# Adafruit_DC_Power_BFF.net
KiCad netlist of a schematic drawn in EAGLE
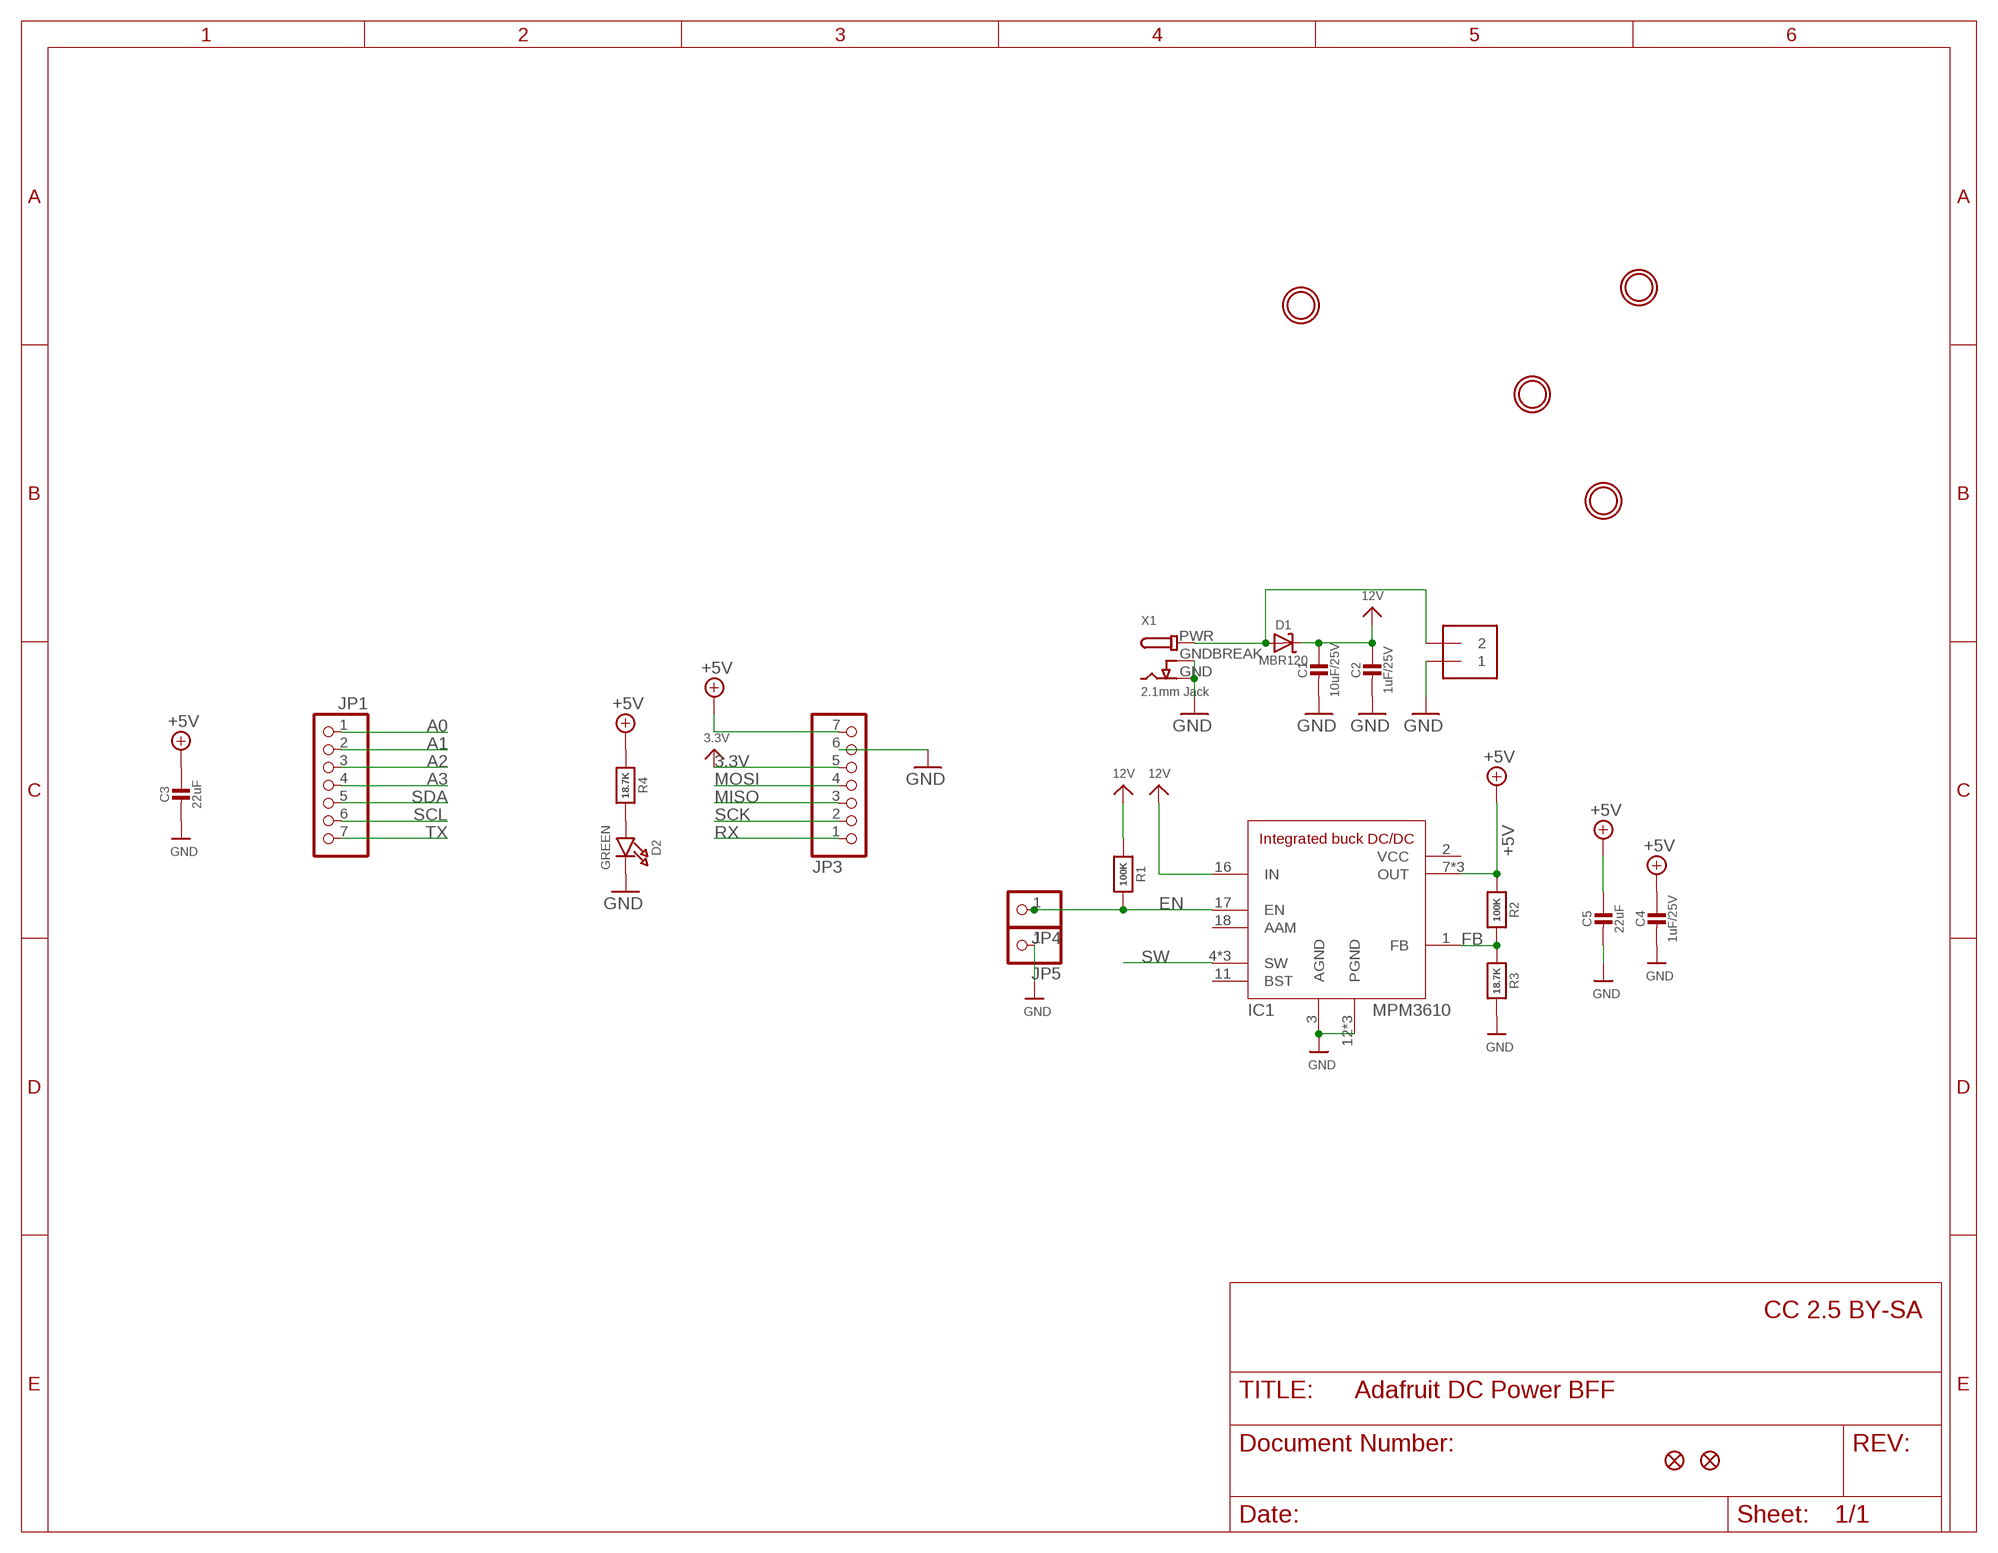
[diagram p0: schematic, sheet 1]

(export (version "E")
  (design (tool "Eeschema 10.0.6"))
  (components
    (comp (ref "C1")
      (value "10uF/25V")
      (footprint "eagle-import:0805-NO")
      (libsource (lib "eagle-import") (part "CAP_CERAMIC0805-NOOUTLINE"))
    )
    (comp (ref "C2")
      (value "1uF/25V")
      (footprint "eagle-import:0603-NO")
      (libsource (lib "eagle-import") (part "CAP_CERAMIC0603_NO"))
    )
    (comp (ref "C3")
      (value "22uF")
      (footprint "eagle-import:0805-NO")
      (libsource (lib "eagle-import") (part "CAP_CERAMIC0805-NOOUTLINE"))
    )
    (comp (ref "C4")
      (value "1uF/25V")
      (footprint "eagle-import:0603-NO")
      (libsource (lib "eagle-import") (part "CAP_CERAMIC0603_NO"))
    )
    (comp (ref "C5")
      (value "22uF")
      (footprint "eagle-import:0805-NO")
      (libsource (lib "eagle-import") (part "CAP_CERAMIC0805-NOOUTLINE"))
    )
    (comp (ref "D1")
      (value "MBR120")
      (footprint "eagle-import:SOD-123FL")
      (libsource (lib "eagle-import") (part "DIODE-SCHOTTKYSOD-123FL"))
    )
    (comp (ref "D2")
      (value "GREEN")
      (footprint "eagle-import:CHIPLED_0603_NOOUTLINE")
      (libsource (lib "eagle-import") (part "LED0603_NOOUTLINE"))
    )
    (comp (ref "IC1")
      (value "MPM3610")
      (footprint "eagle-import:MPM3610")
      (libsource (lib "eagle-import") (part "MPM3610"))
    )
    (comp (ref "J1")
      (value "1X2-3.5MM")
      (footprint "eagle-import:1X2-3.5MM")
      (libsource (lib "eagle-import") (part "1X2-3.5MM"))
    )
    (comp (ref "JP1")
      (value "HEADER-1X7THICKER")
      (footprint "eagle-import:1X07_ROUND_76")
      (libsource (lib "eagle-import") (part "HEADER-1X7THICKER"))
    )
    (comp (ref "JP3")
      (value "HEADER-1X7THICKER")
      (footprint "eagle-import:1X07_ROUND_76")
      (libsource (lib "eagle-import") (part "HEADER-1X7THICKER"))
    )
    (comp (ref "JP4")
      (value "HEADER-1X12MM")
      (footprint "eagle-import:1X01_2MM")
      (libsource (lib "eagle-import") (part "HEADER-1X12MM"))
    )
    (comp (ref "JP5")
      (value "HEADER-1X12MM")
      (footprint "eagle-import:1X01_2MM")
      (libsource (lib "eagle-import") (part "HEADER-1X12MM"))
    )
    (comp (ref "R1")
      (value "100K")
      (footprint "eagle-import:_0402NO")
      (libsource (lib "eagle-import") (part "RESISTOR_0402NO"))
    )
    (comp (ref "R2")
      (value "100K")
      (footprint "eagle-import:_0402NO")
      (libsource (lib "eagle-import") (part "RESISTOR_0402NO"))
    )
    (comp (ref "R3")
      (value "18.7K")
      (footprint "eagle-import:_0402NO")
      (libsource (lib "eagle-import") (part "RESISTOR_0402NO"))
    )
    (comp (ref "R4")
      (value "18.7K")
      (footprint "eagle-import:_0402NO")
      (libsource (lib "eagle-import") (part "RESISTOR_0402NO"))
    )
    (comp (ref "U$6")
      (value "FIDUCIAL_1MM")
      (footprint "eagle-import:FIDUCIAL_1MM")
      (libsource (lib "eagle-import") (part "FIDUCIAL_1MM"))
    )
    (comp (ref "U$8")
      (value "FIDUCIAL_1MM")
      (footprint "eagle-import:FIDUCIAL_1MM")
      (libsource (lib "eagle-import") (part "FIDUCIAL_1MM"))
    )
    (comp (ref "U$14")
      (value "MOUNTINGHOLE2.5")
      (footprint "eagle-import:MOUNTINGHOLE_2.5_PLATED")
      (libsource (lib "eagle-import") (part "MOUNTINGHOLE2.5"))
    )
    (comp (ref "U$15")
      (value "MOUNTINGHOLE2.5")
      (footprint "eagle-import:MOUNTINGHOLE_2.5_PLATED")
      (libsource (lib "eagle-import") (part "MOUNTINGHOLE2.5"))
    )
    (comp (ref "U$17")
      (value "MOUNTINGHOLE2.5")
      (footprint "eagle-import:MOUNTINGHOLE_2.5_PLATED")
      (libsource (lib "eagle-import") (part "MOUNTINGHOLE2.5"))
    )
    (comp (ref "U$18")
      (value "MOUNTINGHOLE2.5")
      (footprint "eagle-import:MOUNTINGHOLE_2.5_PLATED")
      (libsource (lib "eagle-import") (part "MOUNTINGHOLE2.5"))
    )
    (comp (ref "X1")
      (value "2.1mm Jack")
      (footprint "eagle-import:DCJACK_2MM_PTH")
      (libsource (lib "eagle-import") (part "DCBARRELPTH"))
    )
  )
  (nets
    (net (code "1") (name "+5V") (class "Default")
      (node (ref "C3") (pin "1") (pinfunction "1_1") (pintype "passive"))
      (node (ref "C4") (pin "1") (pinfunction "1_1") (pintype "passive"))
      (node (ref "C5") (pin "1") (pinfunction "1_1") (pintype "passive"))
      (node (ref "IC1") (pin "7") (pinfunction "OUT_7") (pintype "power_in"))
      (node (ref "IC1") (pin "8") (pinfunction "OUT_8") (pintype "power_in"))
      (node (ref "IC1") (pin "9") (pinfunction "OUT_9") (pintype "power_in"))
      (node (ref "JP3") (pin "7") (pinfunction "7_7") (pintype "passive"))
      (node (ref "R2") (pin "1") (pinfunction "1_1") (pintype "passive"))
      (node (ref "R4") (pin "1") (pinfunction "1_1") (pintype "passive"))
    )
    (net (code "2") (name "/A0") (class "Default")
      (node (ref "JP1") (pin "1") (pinfunction "1_1") (pintype "passive"))
    )
    (net (code "3") (name "/A1") (class "Default")
      (node (ref "JP1") (pin "2") (pinfunction "2_2") (pintype "passive"))
    )
    (net (code "4") (name "/A2") (class "Default")
      (node (ref "JP1") (pin "3") (pinfunction "3_3") (pintype "passive"))
    )
    (net (code "5") (name "/A3") (class "Default")
      (node (ref "JP1") (pin "4") (pinfunction "4_4") (pintype "passive"))
    )
    (net (code "6") (name "/EN") (class "Default")
      (node (ref "IC1") (pin "17") (pinfunction "EN_17") (pintype "input"))
      (node (ref "JP4") (pin "1") (pinfunction "1_1") (pintype "passive"))
      (node (ref "R1") (pin "2") (pinfunction "2_2") (pintype "passive"))
    )
    (net (code "7") (name "/FB") (class "Default")
      (node (ref "IC1") (pin "1") (pinfunction "FB_1") (pintype "input"))
      (node (ref "R2") (pin "2") (pinfunction "2_2") (pintype "passive"))
      (node (ref "R3") (pin "1") (pinfunction "1_1") (pintype "passive"))
    )
    (net (code "8") (name "/MISO") (class "Default")
      (node (ref "JP3") (pin "3") (pinfunction "3_3") (pintype "passive"))
    )
    (net (code "9") (name "/MOSI") (class "Default")
      (node (ref "JP3") (pin "4") (pinfunction "4_4") (pintype "passive"))
    )
    (net (code "10") (name "/RX") (class "Default")
      (node (ref "JP3") (pin "1") (pinfunction "1_1") (pintype "passive"))
    )
    (net (code "11") (name "/SCK") (class "Default")
      (node (ref "JP3") (pin "2") (pinfunction "2_2") (pintype "passive"))
    )
    (net (code "12") (name "/SCL") (class "Default")
      (node (ref "JP1") (pin "6") (pinfunction "6_6") (pintype "passive"))
    )
    (net (code "13") (name "/SDA") (class "Default")
      (node (ref "JP1") (pin "5") (pinfunction "5_5") (pintype "passive"))
    )
    (net (code "14") (name "/SW") (class "Default")
      (node (ref "IC1") (pin "4") (pinfunction "SW_4") (pintype "passive"))
      (node (ref "IC1") (pin "5") (pinfunction "SW_5") (pintype "passive"))
      (node (ref "IC1") (pin "6") (pinfunction "SW_6") (pintype "passive"))
    )
    (net (code "15") (name "/TX") (class "Default")
      (node (ref "JP1") (pin "7") (pinfunction "7_7") (pintype "passive"))
    )
    (net (code "16") (name "/VCC") (class "Default")
      (node (ref "IC1") (pin "2") (pinfunction "VCC_2") (pintype "power_in"))
    )
    (net (code "17") (name "3.3V") (class "Default")
      (node (ref "JP3") (pin "5") (pinfunction "5_5") (pintype "passive"))
    )
    (net (code "18") (name "12V") (class "Default")
      (node (ref "C1") (pin "1") (pinfunction "1_1") (pintype "passive"))
      (node (ref "C2") (pin "1") (pinfunction "1_1") (pintype "passive"))
      (node (ref "D1") (pin "C") (pinfunction "C_C") (pintype "passive"))
      (node (ref "IC1") (pin "16") (pinfunction "IN_16") (pintype "power_in"))
      (node (ref "R1") (pin "1") (pinfunction "1_1") (pintype "passive"))
    )
    (net (code "19") (name "GND") (class "Default")
      (node (ref "C1") (pin "2") (pinfunction "2_2") (pintype "passive"))
      (node (ref "C2") (pin "2") (pinfunction "2_2") (pintype "passive"))
      (node (ref "C3") (pin "2") (pinfunction "2_2") (pintype "passive"))
      (node (ref "C4") (pin "2") (pinfunction "2_2") (pintype "passive"))
      (node (ref "C5") (pin "2") (pinfunction "2_2") (pintype "passive"))
      (node (ref "D2") (pin "C") (pinfunction "C_C") (pintype "passive"))
      (node (ref "IC1") (pin "12") (pinfunction "PGND_12") (pintype "power_in"))
      (node (ref "IC1") (pin "13") (pinfunction "PGND_13") (pintype "power_in"))
      (node (ref "IC1") (pin "14") (pinfunction "PGND_14") (pintype "power_in"))
      (node (ref "IC1") (pin "3") (pinfunction "AGND_3") (pintype "power_in"))
      (node (ref "J1") (pin "1") (pinfunction "1_1") (pintype "passive"))
      (node (ref "JP3") (pin "6") (pinfunction "6_6") (pintype "passive"))
      (node (ref "JP5") (pin "1") (pinfunction "1_1") (pintype "passive"))
      (node (ref "R3") (pin "2") (pinfunction "2_2") (pintype "passive"))
      (node (ref "X1") (pin "GND") (pinfunction "GND_GND") (pintype "power_in"))
      (node (ref "X1") (pin "GNDBREAK") (pinfunction "GNDBREAK_GNDBREAK") (pintype "power_in"))
    )
    (net (code "20") (name "Net-(D1-PadA)") (class "Default")
      (node (ref "D1") (pin "A") (pinfunction "A_A") (pintype "passive"))
      (node (ref "J1") (pin "2") (pinfunction "2_2") (pintype "passive"))
      (node (ref "X1") (pin "PWR") (pinfunction "PWR_PWR") (pintype "power_in"))
    )
    (net (code "21") (name "Net-(D2-PadA)") (class "Default")
      (node (ref "D2") (pin "A") (pinfunction "A_A") (pintype "passive"))
      (node (ref "R4") (pin "2") (pinfunction "2_2") (pintype "passive"))
    )
    (net (code "22") (name "unconnected-(IC1-AAM-Pad18)") (class "Default")
      (node (ref "IC1") (pin "18") (pinfunction "AAM_18") (pintype "input"))
    )
    (net (code "23") (name "unconnected-(IC1-BST-Pad11)") (class "Default")
      (node (ref "IC1") (pin "11") (pinfunction "BST_11") (pintype "passive"))
    )
  )
)
